# REV002.net
KiCad netlist of a schematic drawn in EAGLE
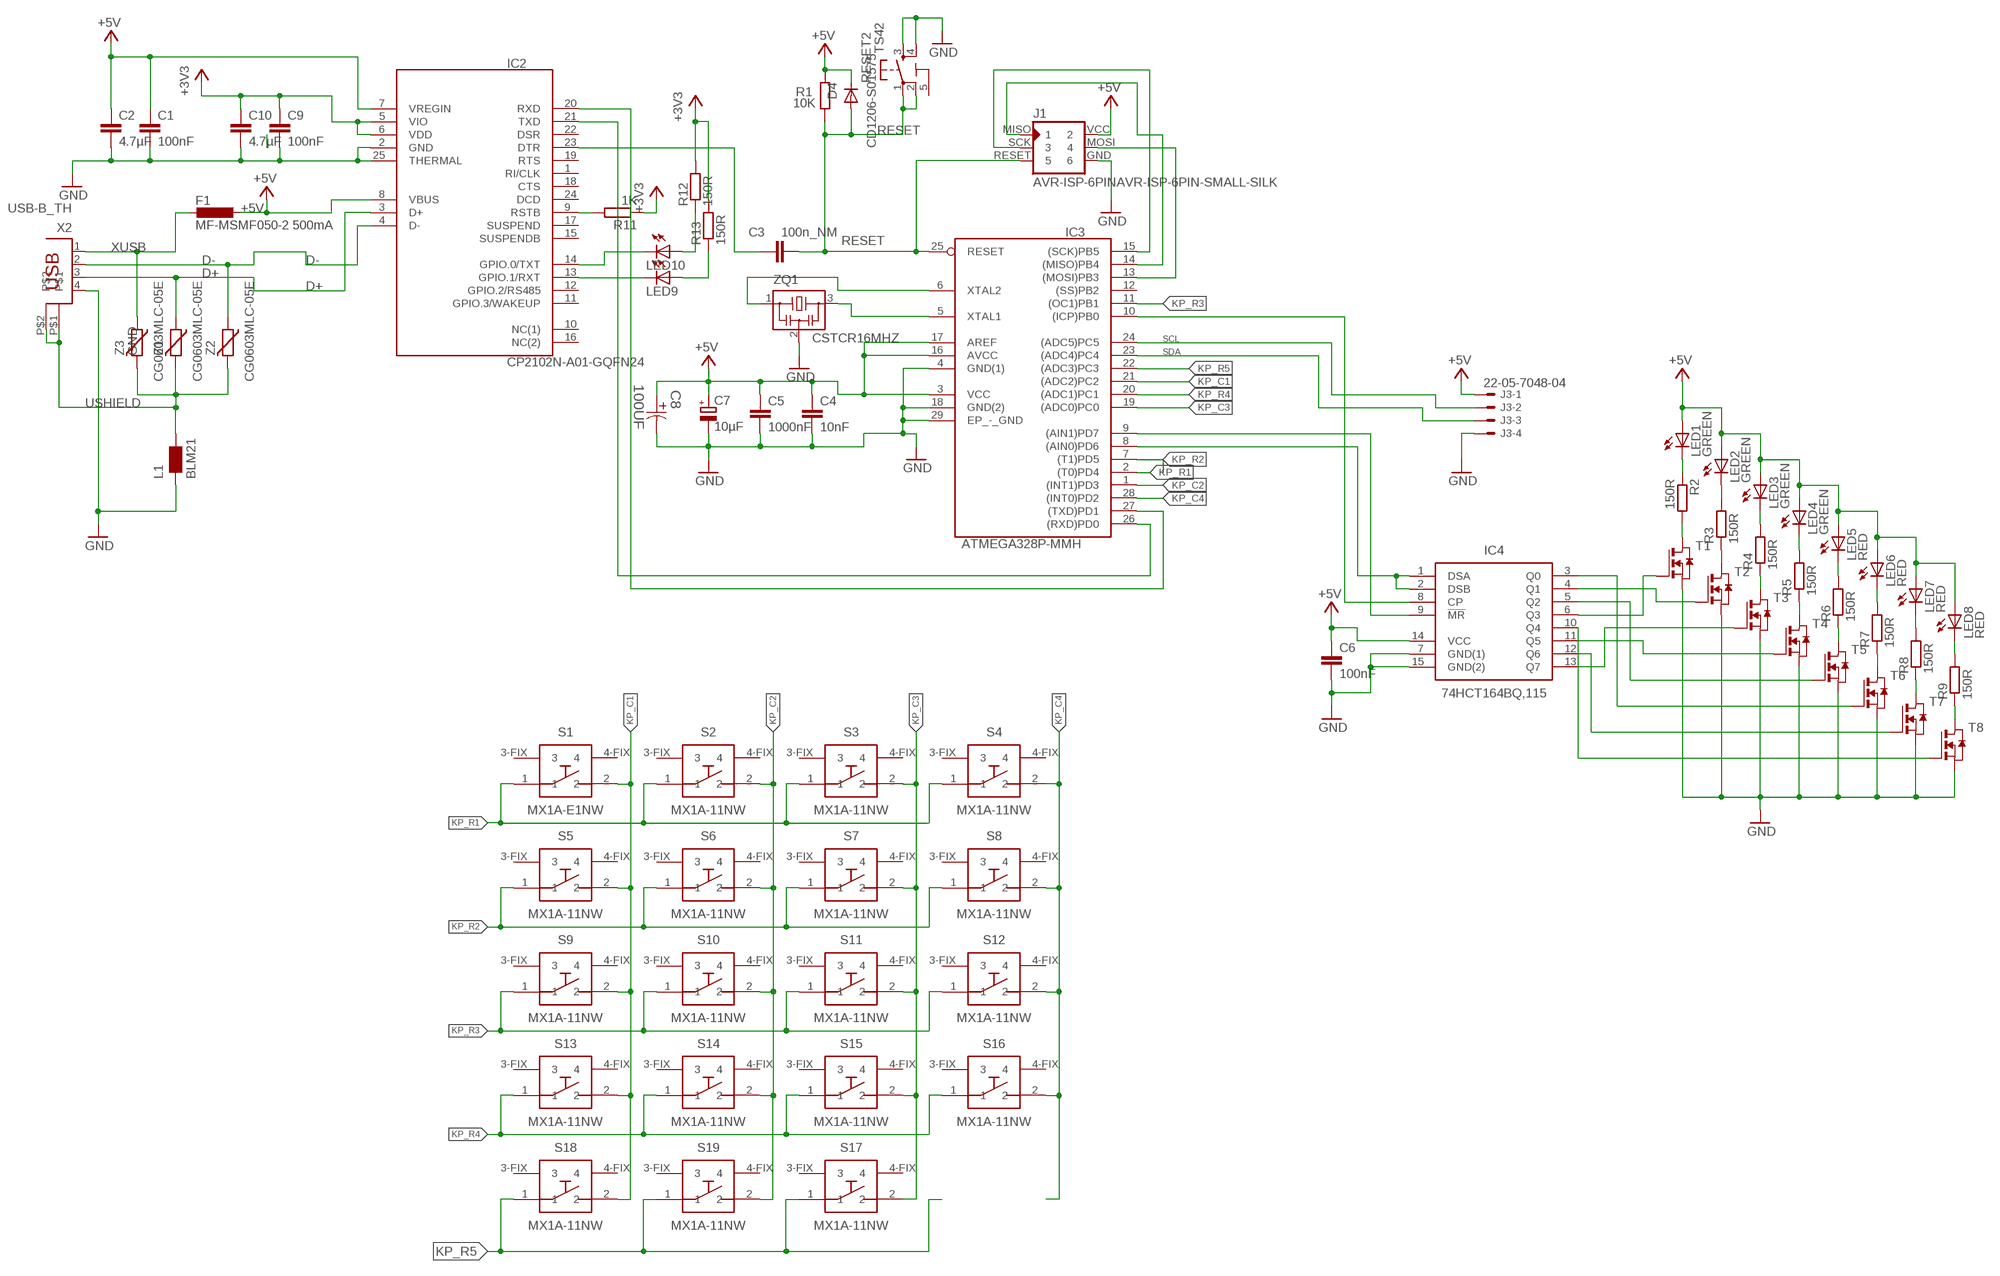
[diagram p0: schematic, sheet 1]

(export (version "E")
  (design (tool "Eeschema 10.0.6"))
  (components
    (comp (ref "C1")
      (value "100nF")
      (footprint "eagle-import:C0603K")
      (libsource (lib "eagle-import") (part "rcl_C-EUC0603K"))
    )
    (comp (ref "C2")
      (value "4.7µF")
      (footprint "eagle-import:C0603K")
      (libsource (lib "eagle-import") (part "rcl_C-EUC0603K"))
    )
    (comp (ref "C3")
      (value "100n_NM")
      (footprint "eagle-import:C0603K")
      (libsource (lib "eagle-import") (part "C-EUC0603K"))
    )
    (comp (ref "C4")
      (value "10nF")
      (footprint "eagle-import:C0603K")
      (libsource (lib "eagle-import") (part "rcl_C-EUC0603K"))
    )
    (comp (ref "C5")
      (value "1000nF")
      (footprint "eagle-import:C0603K")
      (libsource (lib "eagle-import") (part "rcl_C-EUC0603K"))
    )
    (comp (ref "C6")
      (value "100nF")
      (footprint "eagle-import:C0603K")
      (libsource (lib "eagle-import") (part "rcl_C-EUC0603K"))
    )
    (comp (ref "C7")
      (value "10µF")
      (footprint "eagle-import:SMC_B")
      (libsource (lib "eagle-import") (part "CPOL-EUSMCB"))
    )
    (comp (ref "C8")
      (value "100UF")
      (footprint "eagle-import:CAPAE430X610N")
      (fields (field (name "MPN") "EEE-FT0J101AR ") (field (name "TOLERANCE") "±20 %"))
      (libsource (lib "eagle-import") (part "EEE--CASE-BFT0J101AR"))
    )
    (comp (ref "C9")
      (value "100nF")
      (footprint "eagle-import:C0603K")
      (libsource (lib "eagle-import") (part "rcl_C-EUC0603K"))
    )
    (comp (ref "C10")
      (value "4.7µF")
      (footprint "eagle-import:C0603K")
      (libsource (lib "eagle-import") (part "rcl_C-EUC0603K"))
    )
    (comp (ref "D4")
      (value "CD1206-S01575")
      (footprint "eagle-import:MINIMELF")
      (libsource (lib "eagle-import") (part "DIODE-MINIMELF"))
    )
    (comp (ref "F1")
      (value "MF-MSMF050-2 500mA")
      (footprint "eagle-import:L1812")
      (libsource (lib "eagle-import") (part "L-EUL1812"))
    )
    (comp (ref "IC2")
      (value "CP2102N-A01-GQFN24")
      (footprint "eagle-import:QFN50P400X400X80-25N")
      (libsource (lib "eagle-import") (part "CP2102N-A01-GQFN24"))
    )
    (comp (ref "IC3")
      (value "ATMEGA328P-MMH")
      (footprint "eagle-import:QFN45P400X400X100-29N")
      (fields (field (name "RS_PART_NUMBER") "8149138P"))
      (libsource (lib "eagle-import") (part "ATMEGA328P-MMH"))
    )
    (comp (ref "IC4")
      (value "74HCT164BQ,115")
      (footprint "eagle-import:QFN50P300X250X100-15N")
      (libsource (lib "eagle-import") (part "74HCT164BQ,115"))
    )
    (comp (ref "J1")
      (value "AVR-ISP-6PINAVR-ISP-6PIN-SMALL-SILK")
      (footprint "eagle-import:AVR-ISP-6PIN-SMAILL-SILK")
      (libsource (lib "eagle-import") (part "AVR-ISP-6PINAVR-ISP-6PIN-SMALL-SILK"))
    )
    (comp (ref "J3")
      (value "22-05-7048-04")
      (footprint "eagle-import:7395-04")
      (libsource (lib "eagle-import") (part "22-?-0405-7048"))
    )
    (comp (ref "L1")
      (value "BLM21")
      (footprint "eagle-import:0805")
      (libsource (lib "eagle-import") (part "WE-CBF_0805"))
    )
    (comp (ref "LED1")
      (value "GREEN")
      (footprint "eagle-import:P-LCC-2")
      (libsource (lib "eagle-import") (part "LEDP-LCC-2"))
    )
    (comp (ref "LED2")
      (value "GREEN")
      (footprint "eagle-import:P-LCC-2")
      (libsource (lib "eagle-import") (part "LEDP-LCC-2"))
    )
    (comp (ref "LED3")
      (value "GREEN")
      (footprint "eagle-import:P-LCC-2")
      (libsource (lib "eagle-import") (part "LEDP-LCC-2"))
    )
    (comp (ref "LED4")
      (value "GREEN")
      (footprint "eagle-import:P-LCC-2")
      (libsource (lib "eagle-import") (part "LEDP-LCC-2"))
    )
    (comp (ref "LED5")
      (value "RED")
      (footprint "eagle-import:P-LCC-2")
      (libsource (lib "eagle-import") (part "LEDP-LCC-2"))
    )
    (comp (ref "LED6")
      (value "RED")
      (footprint "eagle-import:P-LCC-2")
      (libsource (lib "eagle-import") (part "LEDP-LCC-2"))
    )
    (comp (ref "LED7")
      (value "RED")
      (footprint "eagle-import:P-LCC-2")
      (libsource (lib "eagle-import") (part "LEDP-LCC-2"))
    )
    (comp (ref "LED8")
      (value "RED")
      (footprint "eagle-import:P-LCC-2")
      (libsource (lib "eagle-import") (part "LEDP-LCC-2"))
    )
    (comp (ref "LED9")
      (value "LEDCHIPLED_0603")
      (footprint "eagle-import:CHIPLED_0603")
      (libsource (lib "eagle-import") (part "led_LEDCHIPLED_0603"))
    )
    (comp (ref "LED10")
      (value "LEDCHIPLED_0603")
      (footprint "eagle-import:CHIPLED_0603")
      (libsource (lib "eagle-import") (part "led_LEDCHIPLED_0603"))
    )
    (comp (ref "R1")
      (value "10K")
      (footprint "eagle-import:R0603")
      (libsource (lib "eagle-import") (part "R-EU_R0603"))
    )
    (comp (ref "R2")
      (value "150R")
      (footprint "eagle-import:R0603")
      (libsource (lib "eagle-import") (part "R-EU_R0603"))
    )
    (comp (ref "R3")
      (value "150R")
      (footprint "eagle-import:R0603")
      (libsource (lib "eagle-import") (part "R-EU_R0603"))
    )
    (comp (ref "R4")
      (value "150R")
      (footprint "eagle-import:R0603")
      (libsource (lib "eagle-import") (part "R-EU_R0603"))
    )
    (comp (ref "R5")
      (value "150R")
      (footprint "eagle-import:R0603")
      (libsource (lib "eagle-import") (part "R-EU_R0603"))
    )
    (comp (ref "R6")
      (value "150R")
      (footprint "eagle-import:R0603")
      (libsource (lib "eagle-import") (part "R-EU_R0603"))
    )
    (comp (ref "R7")
      (value "150R")
      (footprint "eagle-import:R0603")
      (libsource (lib "eagle-import") (part "R-EU_R0603"))
    )
    (comp (ref "R8")
      (value "150R")
      (footprint "eagle-import:R0603")
      (libsource (lib "eagle-import") (part "R-EU_R0603"))
    )
    (comp (ref "R9")
      (value "150R")
      (footprint "eagle-import:R0603")
      (libsource (lib "eagle-import") (part "R-EU_R0603"))
    )
    (comp (ref "R11")
      (value "1K")
      (footprint "eagle-import:R0603")
      (libsource (lib "eagle-import") (part "R-EU_R0603"))
    )
    (comp (ref "R12")
      (value "150R")
      (footprint "eagle-import:R0603")
      (libsource (lib "eagle-import") (part "R-EU_R0603"))
    )
    (comp (ref "R13")
      (value "150R")
      (footprint "eagle-import:R0603")
      (libsource (lib "eagle-import") (part "R-EU_R0603"))
    )
    (comp (ref "RESET2")
      (value "TS42")
      (footprint "eagle-import:TS42")
      (libsource (lib "eagle-import") (part "TS42"))
    )
    (comp (ref "S1")
      (value "MX1A-E1NW")
      (footprint "eagle-import:MX1A-11NW_1")
      (fields (field (name "MANUFACTURER_PART_NUMBER") "MX1A-11NW"))
      (libsource (lib "eagle-import") (part "MX1A-11NW"))
    )
    (comp (ref "S2")
      (value "MX1A-11NW")
      (footprint "eagle-import:MX1A-11NW_1")
      (libsource (lib "eagle-import") (part "MX1A-11NW"))
    )
    (comp (ref "S3")
      (value "MX1A-11NW")
      (footprint "eagle-import:MX1A-11NW_1")
      (libsource (lib "eagle-import") (part "MX1A-11NW"))
    )
    (comp (ref "S4")
      (value "MX1A-11NW")
      (footprint "eagle-import:MX1A-11NW_1")
      (libsource (lib "eagle-import") (part "MX1A-11NW"))
    )
    (comp (ref "S5")
      (value "MX1A-11NW")
      (footprint "eagle-import:MX1A-11NW_1")
      (libsource (lib "eagle-import") (part "MX1A-11NW"))
    )
    (comp (ref "S6")
      (value "MX1A-11NW")
      (footprint "eagle-import:MX1A-11NW_1")
      (libsource (lib "eagle-import") (part "MX1A-11NW"))
    )
    (comp (ref "S7")
      (value "MX1A-11NW")
      (footprint "eagle-import:MX1A-11NW_1")
      (libsource (lib "eagle-import") (part "MX1A-11NW"))
    )
    (comp (ref "S8")
      (value "MX1A-11NW")
      (footprint "eagle-import:MX1A-11NW_1")
      (libsource (lib "eagle-import") (part "MX1A-11NW"))
    )
    (comp (ref "S9")
      (value "MX1A-11NW")
      (footprint "eagle-import:MX1A-11NW_1")
      (libsource (lib "eagle-import") (part "MX1A-11NW"))
    )
    (comp (ref "S10")
      (value "MX1A-11NW")
      (footprint "eagle-import:MX1A-11NW_1")
      (libsource (lib "eagle-import") (part "MX1A-11NW"))
    )
    (comp (ref "S11")
      (value "MX1A-11NW")
      (footprint "eagle-import:MX1A-11NW_1")
      (libsource (lib "eagle-import") (part "MX1A-11NW"))
    )
    (comp (ref "S12")
      (value "MX1A-11NW")
      (footprint "eagle-import:MX1A-11NW_1")
      (libsource (lib "eagle-import") (part "MX1A-11NW"))
    )
    (comp (ref "S13")
      (value "MX1A-11NW")
      (footprint "eagle-import:MX1A-11NW_1")
      (libsource (lib "eagle-import") (part "MX1A-11NW"))
    )
    (comp (ref "S14")
      (value "MX1A-11NW")
      (footprint "eagle-import:MX1A-11NW_1")
      (libsource (lib "eagle-import") (part "MX1A-11NW"))
    )
    (comp (ref "S15")
      (value "MX1A-11NW")
      (footprint "eagle-import:MX1A-11NW_1")
      (libsource (lib "eagle-import") (part "MX1A-11NW"))
    )
    (comp (ref "S16")
      (value "MX1A-11NW")
      (footprint "eagle-import:MX1A-11NW_1")
      (libsource (lib "eagle-import") (part "MX1A-11NW"))
    )
    (comp (ref "S17")
      (value "MX1A-11NW")
      (footprint "eagle-import:MX1A-11NW_1")
      (libsource (lib "eagle-import") (part "MX1A-11NW"))
    )
    (comp (ref "S18")
      (value "MX1A-11NW")
      (footprint "eagle-import:MX1A-11NW_1")
      (libsource (lib "eagle-import") (part "MX1A-11NW"))
    )
    (comp (ref "S19")
      (value "MX1A-11NW")
      (footprint "eagle-import:MX1A-11NW_1")
      (libsource (lib "eagle-import") (part "MX1A-11NW"))
    )
    (comp (ref "T1")
      (value "NMOSSOT23")
      (footprint "eagle-import:SOT-23")
      (libsource (lib "eagle-import") (part "NMOSSOT23"))
    )
    (comp (ref "T2")
      (value "NMOSSOT23")
      (footprint "eagle-import:SOT-23")
      (libsource (lib "eagle-import") (part "NMOSSOT23"))
    )
    (comp (ref "T3")
      (value "NMOSSOT23")
      (footprint "eagle-import:SOT-23")
      (libsource (lib "eagle-import") (part "NMOSSOT23"))
    )
    (comp (ref "T4")
      (value "NMOSSOT23")
      (footprint "eagle-import:SOT-23")
      (libsource (lib "eagle-import") (part "NMOSSOT23"))
    )
    (comp (ref "T5")
      (value "NMOSSOT23")
      (footprint "eagle-import:SOT-23")
      (libsource (lib "eagle-import") (part "NMOSSOT23"))
    )
    (comp (ref "T6")
      (value "NMOSSOT23")
      (footprint "eagle-import:SOT-23")
      (libsource (lib "eagle-import") (part "NMOSSOT23"))
    )
    (comp (ref "T7")
      (value "NMOSSOT23")
      (footprint "eagle-import:SOT-23")
      (libsource (lib "eagle-import") (part "NMOSSOT23"))
    )
    (comp (ref "T8")
      (value "NMOSSOT23")
      (footprint "eagle-import:SOT-23")
      (libsource (lib "eagle-import") (part "NMOSSOT23"))
    )
    (comp (ref "X2")
      (value "USB-B_TH")
      (footprint "eagle-import:PN61729")
      (libsource (lib "eagle-import") (part "PN61729"))
    )
    (comp (ref "Z1")
      (value "CG0603MLC-05E")
      (footprint "eagle-import:CT_CN0603")
      (libsource (lib "eagle-import") (part "VARISTORCN0603"))
    )
    (comp (ref "Z2")
      (value "CG0603MLC-05E")
      (footprint "eagle-import:CT_CN0603")
      (libsource (lib "eagle-import") (part "VARISTORCN0603"))
    )
    (comp (ref "Z3")
      (value "CG0603MLC-05E")
      (footprint "eagle-import:CT_CN0603")
      (libsource (lib "eagle-import") (part "VARISTORCN0603"))
    )
    (comp (ref "ZQ1")
      (value "CSTCR16MHZ")
      (footprint "eagle-import:CSTER12M")
      (libsource (lib "eagle-import") (part "CSTC?R"))
    )
  )
  (nets
    (net (code "1") (name "+3V3") (class "Default")
      (node (ref "C10") (pin "1") (pinfunction "1_1") (pintype "passive"))
      (node (ref "C9") (pin "1") (pinfunction "1_1") (pintype "passive"))
      (node (ref "IC2") (pin "5") (pinfunction "VIO_5") (pintype "input"))
      (node (ref "IC2") (pin "6") (pinfunction "VDD_6") (pintype "input"))
      (node (ref "R11") (pin "1") (pinfunction "1_1") (pintype "passive"))
      (node (ref "R12") (pin "2") (pinfunction "2_2") (pintype "passive"))
      (node (ref "R13") (pin "2") (pinfunction "2_2") (pintype "passive"))
    )
    (net (code "2") (name "+5V") (class "Default")
      (node (ref "C1") (pin "1") (pinfunction "1_1") (pintype "passive"))
      (node (ref "C2") (pin "1") (pinfunction "1_1") (pintype "passive"))
      (node (ref "C4") (pin "1") (pinfunction "1_1") (pintype "passive"))
      (node (ref "C5") (pin "1") (pinfunction "1_1") (pintype "passive"))
      (node (ref "C6") (pin "1") (pinfunction "1_1") (pintype "passive"))
      (node (ref "C7") (pin "+") (pinfunction "+_+") (pintype "passive"))
      (node (ref "C8") (pin "1") (pinfunction "1_1") (pintype "passive"))
      (node (ref "D4") (pin "C") (pinfunction "C_C") (pintype "passive"))
      (node (ref "F1") (pin "1") (pinfunction "1_1") (pintype "passive"))
      (node (ref "IC2") (pin "7") (pinfunction "VREGIN_7") (pintype "input"))
      (node (ref "IC2") (pin "8") (pinfunction "VBUS_8") (pintype "input"))
      (node (ref "IC3") (pin "16") (pinfunction "AVCC_16") (pintype "input"))
      (node (ref "IC3") (pin "17") (pinfunction "AREF_17") (pintype "input"))
      (node (ref "IC3") (pin "3") (pinfunction "VCC_3") (pintype "input"))
      (node (ref "IC4") (pin "14") (pinfunction "VCC_14") (pintype "input"))
      (node (ref "J1") (pin "VCC") (pinfunction "2_VCC") (pintype "passive"))
      (node (ref "J3") (pin "1") (pinfunction "S_1") (pintype "passive"))
      (node (ref "LED1") (pin "A") (pinfunction "A_A") (pintype "passive"))
      (node (ref "LED2") (pin "A") (pinfunction "A_A") (pintype "passive"))
      (node (ref "LED3") (pin "A") (pinfunction "A_A") (pintype "passive"))
      (node (ref "LED4") (pin "A") (pinfunction "A_A") (pintype "passive"))
      (node (ref "LED5") (pin "A") (pinfunction "A_A") (pintype "passive"))
      (node (ref "LED6") (pin "A") (pinfunction "A_A") (pintype "passive"))
      (node (ref "LED7") (pin "A") (pinfunction "A_A") (pintype "passive"))
      (node (ref "LED8") (pin "A") (pinfunction "A_A") (pintype "passive"))
      (node (ref "R1") (pin "2") (pinfunction "2_2") (pintype "passive"))
    )
    (net (code "3") (name "/5-GND") (class "Default")
      (node (ref "RESET2") (pin "5") (pinfunction "5-GND_5") (pintype "power_in"))
    )
    (net (code "4") (name "/D+") (class "Default")
      (node (ref "IC2") (pin "3") (pinfunction "D+_3") (pintype "input"))
      (node (ref "X2") (pin "3") (pinfunction "3_3") (pintype "bidirectional"))
      (node (ref "Z1") (pin "1") (pinfunction "1_1") (pintype "passive"))
    )
    (net (code "5") (name "/D-") (class "Default")
      (node (ref "IC2") (pin "4") (pinfunction "D-_4") (pintype "input"))
      (node (ref "X2") (pin "2") (pinfunction "2_2") (pintype "bidirectional"))
      (node (ref "Z2") (pin "1") (pinfunction "1_1") (pintype "passive"))
    )
    (net (code "6") (name "/RESET") (class "Default")
      (node (ref "C3") (pin "1") (pinfunction "1_1") (pintype "passive"))
      (node (ref "D4") (pin "A") (pinfunction "A_A") (pintype "passive"))
      (node (ref "IC3") (pin "25") (pinfunction "RESET_25") (pintype "input"))
      (node (ref "J1") (pin "RESET") (pinfunction "5_RESET") (pintype "passive"))
      (node (ref "R1") (pin "1") (pinfunction "1_1") (pintype "passive"))
      (node (ref "RESET2") (pin "1") (pinfunction "1_1") (pintype "passive"))
      (node (ref "RESET2") (pin "2") (pinfunction "2_2") (pintype "passive"))
    )
    (net (code "7") (name "/SCL") (class "Default")
      (node (ref "IC3") (pin "24") (pinfunction "(ADC5)PC5_24") (pintype "input"))
      (node (ref "J3") (pin "2") (pinfunction "S_2") (pintype "passive"))
    )
    (net (code "8") (name "/SDA") (class "Default")
      (node (ref "IC3") (pin "23") (pinfunction "(ADC4)PC4_23") (pintype "input"))
      (node (ref "J3") (pin "3") (pinfunction "S_3") (pintype "passive"))
    )
    (net (code "9") (name "/USHIELD") (class "Default")
      (node (ref "L1") (pin "2") (pinfunction "2_2") (pintype "passive"))
      (node (ref "X2") (pin "P$1") (pinfunction "P$1_P$1") (pintype "bidirectional"))
      (node (ref "X2") (pin "P$2") (pinfunction "P$2_P$2") (pintype "bidirectional"))
      (node (ref "Z1") (pin "2") (pinfunction "2_2") (pintype "passive"))
      (node (ref "Z2") (pin "2") (pinfunction "2_2") (pintype "passive"))
      (node (ref "Z3") (pin "2") (pinfunction "2_2") (pintype "passive"))
    )
    (net (code "10") (name "/XUSB") (class "Default")
      (node (ref "F1") (pin "2") (pinfunction "2_2") (pintype "passive"))
      (node (ref "X2") (pin "1") (pinfunction "1_1") (pintype "bidirectional"))
      (node (ref "Z3") (pin "1") (pinfunction "1_1") (pintype "passive"))
    )
    (net (code "11") (name "GND") (class "Default")
      (node (ref "C1") (pin "2") (pinfunction "2_2") (pintype "passive"))
      (node (ref "C10") (pin "2") (pinfunction "2_2") (pintype "passive"))
      (node (ref "C2") (pin "2") (pinfunction "2_2") (pintype "passive"))
      (node (ref "C4") (pin "2") (pinfunction "2_2") (pintype "passive"))
      (node (ref "C5") (pin "2") (pinfunction "2_2") (pintype "passive"))
      (node (ref "C6") (pin "2") (pinfunction "2_2") (pintype "passive"))
      (node (ref "C7") (pin "-") (pinfunction "-_-") (pintype "passive"))
      (node (ref "C8") (pin "2") (pinfunction "2_2") (pintype "passive"))
      (node (ref "C9") (pin "2") (pinfunction "2_2") (pintype "passive"))
      (node (ref "IC2") (pin "2") (pinfunction "GND_2") (pintype "input"))
      (node (ref "IC2") (pin "25") (pinfunction "THERMAL_25") (pintype "input"))
      (node (ref "IC3") (pin "18") (pinfunction "GND(2)_18") (pintype "input"))
      (node (ref "IC3") (pin "29") (pinfunction "EP_-_GND_29") (pintype "input"))
      (node (ref "IC3") (pin "4") (pinfunction "GND(1)_4") (pintype "input"))
      (node (ref "IC4") (pin "15") (pinfunction "GND(2)_15") (pintype "input"))
      (node (ref "IC4") (pin "7") (pinfunction "GND(1)_7") (pintype "input"))
      (node (ref "J1") (pin "GND") (pinfunction "6_GND") (pintype "passive"))
      (node (ref "J3") (pin "4") (pinfunction "S_4") (pintype "passive"))
      (node (ref "L1") (pin "1") (pinfunction "1_1") (pintype "passive"))
      (node (ref "RESET2") (pin "3") (pinfunction "3_3") (pintype "passive"))
      (node (ref "RESET2") (pin "4") (pinfunction "4_4") (pintype "passive"))
      (node (ref "T1") (pin "2") (pinfunction "S_2") (pintype "passive"))
      (node (ref "T2") (pin "2") (pinfunction "S_2") (pintype "passive"))
      (node (ref "T3") (pin "2") (pinfunction "S_2") (pintype "passive"))
      (node (ref "T4") (pin "2") (pinfunction "S_2") (pintype "passive"))
      (node (ref "T5") (pin "2") (pinfunction "S_2") (pintype "passive"))
      (node (ref "T6") (pin "2") (pinfunction "S_2") (pintype "passive"))
      (node (ref "T7") (pin "2") (pinfunction "S_2") (pintype "passive"))
      (node (ref "T8") (pin "2") (pinfunction "S_2") (pintype "passive"))
      (node (ref "X2") (pin "4") (pinfunction "4_4") (pintype "bidirectional"))
      (node (ref "ZQ1") (pin "2") (pinfunction "2_2") (pintype "passive"))
    )
    (net (code "12") (name "KP_C1") (class "Default")
      (node (ref "IC3") (pin "21") (pinfunction "(ADC2)PC2_21") (pintype "input"))
      (node (ref "S1") (pin "2") (pinfunction "2_2") (pintype "input"))
      (node (ref "S13") (pin "2") (pinfunction "2_2") (pintype "input"))
      (node (ref "S18") (pin "2") (pinfunction "2_2") (pintype "input"))
      (node (ref "S5") (pin "2") (pinfunction "2_2") (pintype "input"))
      (node (ref "S9") (pin "2") (pinfunction "2_2") (pintype "input"))
    )
    (net (code "13") (name "KP_C2") (class "Default")
      (node (ref "IC3") (pin "1") (pinfunction "(INT1)PD3_1") (pintype "input"))
      (node (ref "S10") (pin "2") (pinfunction "2_2") (pintype "input"))
      (node (ref "S14") (pin "2") (pinfunction "2_2") (pintype "input"))
      (node (ref "S19") (pin "2") (pinfunction "2_2") (pintype "input"))
      (node (ref "S2") (pin "2") (pinfunction "2_2") (pintype "input"))
      (node (ref "S6") (pin "2") (pinfunction "2_2") (pintype "input"))
    )
    (net (code "14") (name "KP_C3") (class "Default")
      (node (ref "IC3") (pin "19") (pinfunction "(ADC0)PC0_19") (pintype "input"))
      (node (ref "S11") (pin "2") (pinfunction "2_2") (pintype "input"))
      (node (ref "S15") (pin "2") (pinfunction "2_2") (pintype "input"))
      (node (ref "S17") (pin "2") (pinfunction "2_2") (pintype "input"))
      (node (ref "S3") (pin "2") (pinfunction "2_2") (pintype "input"))
      (node (ref "S7") (pin "2") (pinfunction "2_2") (pintype "input"))
    )
    (net (code "15") (name "KP_C4") (class "Default")
      (node (ref "IC3") (pin "28") (pinfunction "(INT0)PD2_28") (pintype "input"))
      (node (ref "S12") (pin "2") (pinfunction "2_2") (pintype "input"))
      (node (ref "S16") (pin "2") (pinfunction "2_2") (pintype "input"))
      (node (ref "S4") (pin "2") (pinfunction "2_2") (pintype "input"))
      (node (ref "S8") (pin "2") (pinfunction "2_2") (pintype "input"))
    )
    (net (code "16") (name "KP_R1") (class "Default")
      (node (ref "IC3") (pin "2") (pinfunction "(T0)PD4_2") (pintype "input"))
      (node (ref "S1") (pin "1") (pinfunction "1_1") (pintype "input"))
      (node (ref "S2") (pin "1") (pinfunction "1_1") (pintype "input"))
      (node (ref "S3") (pin "1") (pinfunction "1_1") (pintype "input"))
      (node (ref "S4") (pin "1") (pinfunction "1_1") (pintype "input"))
    )
    (net (code "17") (name "KP_R2") (class "Default")
      (node (ref "IC3") (pin "7") (pinfunction "(T1)PD5_7") (pintype "input"))
      (node (ref "S5") (pin "1") (pinfunction "1_1") (pintype "input"))
      (node (ref "S6") (pin "1") (pinfunction "1_1") (pintype "input"))
      (node (ref "S7") (pin "1") (pinfunction "1_1") (pintype "input"))
      (node (ref "S8") (pin "1") (pinfunction "1_1") (pintype "input"))
    )
    (net (code "18") (name "KP_R3") (class "Default")
      (node (ref "IC3") (pin "11") (pinfunction "(OC1)PB1_11") (pintype "input"))
      (node (ref "S10") (pin "1") (pinfunction "1_1") (pintype "input"))
      (node (ref "S11") (pin "1") (pinfunction "1_1") (pintype "input"))
      (node (ref "S12") (pin "1") (pinfunction "1_1") (pintype "input"))
      (node (ref "S9") (pin "1") (pinfunction "1_1") (pintype "input"))
    )
    (net (code "19") (name "KP_R4") (class "Default")
      (node (ref "IC3") (pin "20") (pinfunction "(ADC1)PC1_20") (pintype "input"))
      (node (ref "S13") (pin "1") (pinfunction "1_1") (pintype "input"))
      (node (ref "S14") (pin "1") (pinfunction "1_1") (pintype "input"))
      (node (ref "S15") (pin "1") (pinfunction "1_1") (pintype "input"))
      (node (ref "S16") (pin "1") (pinfunction "1_1") (pintype "input"))
    )
    (net (code "20") (name "KP_R5") (class "Default")
      (node (ref "IC3") (pin "22") (pinfunction "(ADC3)PC3_22") (pintype "input"))
      (node (ref "S17") (pin "1") (pinfunction "1_1") (pintype "input"))
      (node (ref "S18") (pin "1") (pinfunction "1_1") (pintype "input"))
      (node (ref "S19") (pin "1") (pinfunction "1_1") (pintype "input"))
    )
    (net (code "21") (name "Net-(IC2-DTR)") (class "Default")
      (node (ref "C3") (pin "2") (pinfunction "2_2") (pintype "passive"))
      (node (ref "IC2") (pin "23") (pinfunction "DTR_23") (pintype "input"))
    )
    (net (code "22") (name "Net-(IC2-GPIO.0{slash}TXT)") (class "Default")
      (node (ref "IC2") (pin "14") (pinfunction "GPIO.0/TXT_14") (pintype "input"))
      (node (ref "LED10") (pin "C") (pinfunction "C_C") (pintype "passive"))
    )
    (net (code "23") (name "Net-(IC2-GPIO.1{slash}RXT)") (class "Default")
      (node (ref "IC2") (pin "13") (pinfunction "GPIO.1/RXT_13") (pintype "input"))
      (node (ref "LED9") (pin "C") (pinfunction "C_C") (pintype "passive"))
    )
    (net (code "24") (name "Net-(IC2-RSTB)") (class "Default")
      (node (ref "IC2") (pin "9") (pinfunction "RSTB_9") (pintype "input"))
      (node (ref "R11") (pin "2") (pinfunction "2_2") (pintype "passive"))
    )
    (net (code "25") (name "Net-(IC2-RXD)") (class "Default")
      (node (ref "IC2") (pin "20") (pinfunction "RXD_20") (pintype "input"))
      (node (ref "IC3") (pin "27") (pinfunction "(TXD)PD1_27") (pintype "input"))
    )
    (net (code "26") (name "Net-(IC2-TXD)") (class "Default")
      (node (ref "IC2") (pin "21") (pinfunction "TXD_21") (pintype "input"))
      (node (ref "IC3") (pin "26") (pinfunction "(RXD)PD0_26") (pintype "input"))
    )
    (net (code "27") (name "Net-(IC3-(AIN0)PD6)") (class "Default")
      (node (ref "IC3") (pin "8") (pinfunction "(AIN0)PD6_8") (pintype "input"))
      (node (ref "IC4") (pin "1") (pinfunction "DSA_1") (pintype "input"))
      (node (ref "IC4") (pin "2") (pinfunction "DSB_2") (pintype "input"))
    )
    (net (code "28") (name "Net-(IC3-(AIN1)PD7)") (class "Default")
      (node (ref "IC3") (pin "9") (pinfunction "(AIN1)PD7_9") (pintype "input"))
      (node (ref "IC4") (pin "9") (pinfunction "~{MR}_9") (pintype "input"))
    )
    (net (code "29") (name "Net-(IC3-(ICP)PB0)") (class "Default")
      (node (ref "IC3") (pin "10") (pinfunction "(ICP)PB0_10") (pintype "input"))
      (node (ref "IC4") (pin "8") (pinfunction "CP_8") (pintype "input"))
    )
    (net (code "30") (name "Net-(IC3-(MISO)PB4)") (class "Default")
      (node (ref "IC3") (pin "14") (pinfunction "(MISO)PB4_14") (pintype "input"))
      (node (ref "J1") (pin "MISO") (pinfunction "1_MISO") (pintype "passive"))
    )
    (net (code "31") (name "Net-(IC3-(MOSI)PB3)") (class "Default")
      (node (ref "IC3") (pin "13") (pinfunction "(MOSI)PB3_13") (pintype "input"))
      (node (ref "J1") (pin "MOSI") (pinfunction "4_MOSI") (pintype "passive"))
    )
    (net (code "32") (name "Net-(IC3-(SCK)PB5)") (class "Default")
      (node (ref "IC3") (pin "15") (pinfunction "(SCK)PB5_15") (pintype "input"))
      (node (ref "J1") (pin "SCK") (pinfunction "3_SCK") (pintype "passive"))
    )
    (net (code "33") (name "Net-(IC3-XTAL1)") (class "Default")
      (node (ref "IC3") (pin "5") (pinfunction "XTAL1_5") (pintype "input"))
      (node (ref "ZQ1") (pin "3") (pinfunction "3_3") (pintype "passive"))
    )
    (net (code "34") (name "Net-(IC3-XTAL2)") (class "Default")
      (node (ref "IC3") (pin "6") (pinfunction "XTAL2_6") (pintype "input"))
      (node (ref "ZQ1") (pin "1") (pinfunction "1_1") (pintype "passive"))
    )
    (net (code "35") (name "Net-(IC4-Q0)") (class "Default")
      (node (ref "IC4") (pin "3") (pinfunction "Q0_3") (pintype "input"))
      (node (ref "T6") (pin "3") (pinfunction "G_3") (pintype "passive"))
    )
    (net (code "36") (name "Net-(IC4-Q1)") (class "Default")
      (node (ref "IC4") (pin "4") (pinfunction "Q1_4") (pintype "input"))
      (node (ref "T2") (pin "3") (pinfunction "G_3") (pintype "passive"))
    )
    (net (code "37") (name "Net-(IC4-Q2)") (class "Default")
      (node (ref "IC4") (pin "5") (pinfunction "Q2_5") (pintype "input"))
      (node (ref "T5") (pin "3") (pinfunction "G_3") (pintype "passive"))
    )
    (net (code "38") (name "Net-(IC4-Q3)") (class "Default")
      (node (ref "IC4") (pin "6") (pinfunction "Q3_6") (pintype "input"))
      (node (ref "T1") (pin "3") (pinfunction "G_3") (pintype "passive"))
    )
    (net (code "39") (name "Net-(IC4-Q4)") (class "Default")
      (node (ref "IC4") (pin "10") (pinfunction "Q4_10") (pintype "input"))
      (node (ref "T8") (pin "3") (pinfunction "G_3") (pintype "passive"))
    )
    (net (code "40") (name "Net-(IC4-Q5)") (class "Default")
      (node (ref "IC4") (pin "11") (pinfunction "Q5_11") (pintype "input"))
      (node (ref "T4") (pin "3") (pinfunction "G_3") (pintype "passive"))
    )
    (net (code "41") (name "Net-(IC4-Q6)") (class "Default")
      (node (ref "IC4") (pin "12") (pinfunction "Q6_12") (pintype "input"))
      (node (ref "T7") (pin "3") (pinfunction "G_3") (pintype "passive"))
    )
    (net (code "42") (name "Net-(IC4-Q7)") (class "Default")
      (node (ref "IC4") (pin "13") (pinfunction "Q7_13") (pintype "input"))
      (node (ref "T3") (pin "3") (pinfunction "G_3") (pintype "passive"))
    )
    (net (code "43") (name "Net-(LED1-PadC)") (class "Default")
      (node (ref "LED1") (pin "C") (pinfunction "C_C") (pintype "passive"))
      (node (ref "R2") (pin "1") (pinfunction "1_1") (pintype "passive"))
    )
    (net (code "44") (name "Net-(LED2-PadC)") (class "Default")
      (node (ref "LED2") (pin "C") (pinfunction "C_C") (pintype "passive"))
      (node (ref "R3") (pin "2") (pinfunction "2_2") (pintype "passive"))
    )
    (net (code "45") (name "Net-(LED3-PadC)") (class "Default")
      (node (ref "LED3") (pin "C") (pinfunction "C_C") (pintype "passive"))
      (node (ref "R4") (pin "2") (pinfunction "2_2") (pintype "passive"))
    )
    (net (code "46") (name "Net-(LED4-PadC)") (class "Default")
      (node (ref "LED4") (pin "C") (pinfunction "C_C") (pintype "passive"))
      (node (ref "R5") (pin "2") (pinfunction "2_2") (pintype "passive"))
    )
    (net (code "47") (name "Net-(LED5-PadC)") (class "Default")
      (node (ref "LED5") (pin "C") (pinfunction "C_C") (pintype "passive"))
      (node (ref "R6") (pin "2") (pinfunction "2_2") (pintype "passive"))
    )
    (net (code "48") (name "Net-(LED6-PadC)") (class "Default")
      (node (ref "LED6") (pin "C") (pinfunction "C_C") (pintype "passive"))
      (node (ref "R7") (pin "2") (pinfunction "2_2") (pintype "passive"))
    )
    (net (code "49") (name "Net-(LED7-PadC)") (class "Default")
      (node (ref "LED7") (pin "C") (pinfunction "C_C") (pintype "passive"))
      (node (ref "R8") (pin "2") (pinfunction "2_2") (pintype "passive"))
    )
    (net (code "50") (name "Net-(LED8-PadC)") (class "Default")
      (node (ref "LED8") (pin "C") (pinfunction "C_C") (pintype "passive"))
      (node (ref "R9") (pin "2") (pinfunction "2_2") (pintype "passive"))
    )
    (net (code "51") (name "Net-(LED9-PadA)") (class "Default")
      (node (ref "LED9") (pin "A") (pinfunction "A_A") (pintype "passive"))
      (node (ref "R13") (pin "1") (pinfunction "1_1") (pintype "passive"))
    )
    (net (code "52") (name "Net-(LED10-PadA)") (class "Default")
      (node (ref "LED10") (pin "A") (pinfunction "A_A") (pintype "passive"))
      (node (ref "R12") (pin "1") (pinfunction "1_1") (pintype "passive"))
    )
    (net (code "53") (name "Net-(T1-D)") (class "Default")
      (node (ref "R2") (pin "2") (pinfunction "2_2") (pintype "passive"))
      (node (ref "T1") (pin "1") (pinfunction "D_1") (pintype "passive"))
    )
    (net (code "54") (name "Net-(T2-D)") (class "Default")
      (node (ref "R3") (pin "1") (pinfunction "1_1") (pintype "passive"))
      (node (ref "T2") (pin "1") (pinfunction "D_1") (pintype "passive"))
    )
    (net (code "55") (name "Net-(T3-D)") (class "Default")
      (node (ref "R4") (pin "1") (pinfunction "1_1") (pintype "passive"))
      (node (ref "T3") (pin "1") (pinfunction "D_1") (pintype "passive"))
    )
    (net (code "56") (name "Net-(T4-D)") (class "Default")
      (node (ref "R5") (pin "1") (pinfunction "1_1") (pintype "passive"))
      (node (ref "T4") (pin "1") (pinfunction "D_1") (pintype "passive"))
    )
    (net (code "57") (name "Net-(T5-D)") (class "Default")
      (node (ref "R6") (pin "1") (pinfunction "1_1") (pintype "passive"))
      (node (ref "T5") (pin "1") (pinfunction "D_1") (pintype "passive"))
    )
    (net (code "58") (name "Net-(T6-D)") (class "Default")
      (node (ref "R7") (pin "1") (pinfunction "1_1") (pintype "passive"))
      (node (ref "T6") (pin "1") (pinfunction "D_1") (pintype "passive"))
    )
    (net (code "59") (name "Net-(T7-D)") (class "Default")
      (node (ref "R8") (pin "1") (pinfunction "1_1") (pintype "passive"))
      (node (ref "T7") (pin "1") (pinfunction "D_1") (pintype "passive"))
    )
    (net (code "60") (name "Net-(T8-D)") (class "Default")
      (node (ref "R9") (pin "1") (pinfunction "1_1") (pintype "passive"))
      (node (ref "T8") (pin "1") (pinfunction "D_1") (pintype "passive"))
    )
    (net (code "61") (name "unconnected-(IC2-CTS-Pad18)") (class "Default")
      (node (ref "IC2") (pin "18") (pinfunction "CTS_18") (pintype "input"))
    )
    (net (code "62") (name "unconnected-(IC2-DCD-Pad24)") (class "Default")
      (node (ref "IC2") (pin "24") (pinfunction "DCD_24") (pintype "input"))
    )
    (net (code "63") (name "unconnected-(IC2-DSR-Pad22)") (class "Default")
      (node (ref "IC2") (pin "22") (pinfunction "DSR_22") (pintype "input"))
    )
    (net (code "64") (name "unconnected-(IC2-GPIO.2{slash}RS485-Pad12)") (class "Default")
      (node (ref "IC2") (pin "12") (pinfunction "GPIO.2/RS485_12") (pintype "input"))
    )
    (net (code "65") (name "unconnected-(IC2-GPIO.3{slash}WAKEUP-Pad11)") (class "Default")
      (node (ref "IC2") (pin "11") (pinfunction "GPIO.3/WAKEUP_11") (pintype "input"))
    )
    (net (code "66") (name "unconnected-(IC2-NC(1)-Pad10)") (class "Default")
      (node (ref "IC2") (pin "10") (pinfunction "NC(1)_10") (pintype "input"))
    )
    (net (code "67") (name "unconnected-(IC2-NC(2)-Pad16)") (class "Default")
      (node (ref "IC2") (pin "16") (pinfunction "NC(2)_16") (pintype "input"))
    )
    (net (code "68") (name "unconnected-(IC2-RI{slash}CLK-Pad1)") (class "Default")
      (node (ref "IC2") (pin "1") (pinfunction "RI/CLK_1") (pintype "input"))
    )
    (net (code "69") (name "unconnected-(IC2-RTS-Pad19)") (class "Default")
      (node (ref "IC2") (pin "19") (pinfunction "RTS_19") (pintype "input"))
    )
    (net (code "70") (name "unconnected-(IC2-SUSPEND-Pad17)") (class "Default")
      (node (ref "IC2") (pin "17") (pinfunction "SUSPEND_17") (pintype "input"))
    )
    (net (code "71") (name "unconnected-(IC2-SUSPENDB-Pad15)") (class "Default")
      (node (ref "IC2") (pin "15") (pinfunction "SUSPENDB_15") (pintype "input"))
    )
    (net (code "72") (name "unconnected-(IC3-(SS)PB2-Pad12)") (class "Default")
      (node (ref "IC3") (pin "12") (pinfunction "(SS)PB2_12") (pintype "input"))
    )
    (net (code "73") (name "unconnected-(S1-3-Pad3-FIX)") (class "Default")
      (node (ref "S1") (pin "3-FIX") (pinfunction "3_3-FIX") (pintype "input"))
    )
    (net (code "74") (name "unconnected-(S1-4-Pad4-FIX)") (class "Default")
      (node (ref "S1") (pin "4-FIX") (pinfunction "4_4-FIX") (pintype "input"))
    )
    (net (code "75") (name "unconnected-(S2-3-Pad3-FIX)") (class "Default")
      (node (ref "S2") (pin "3-FIX") (pinfunction "3_3-FIX") (pintype "input"))
    )
    (net (code "76") (name "unconnected-(S2-4-Pad4-FIX)") (class "Default")
      (node (ref "S2") (pin "4-FIX") (pinfunction "4_4-FIX") (pintype "input"))
    )
    (net (code "77") (name "unconnected-(S3-3-Pad3-FIX)") (class "Default")
      (node (ref "S3") (pin "3-FIX") (pinfunction "3_3-FIX") (pintype "input"))
    )
    (net (code "78") (name "unconnected-(S3-4-Pad4-FIX)") (class "Default")
      (node (ref "S3") (pin "4-FIX") (pinfunction "4_4-FIX") (pintype "input"))
    )
    (net (code "79") (name "unconnected-(S4-3-Pad3-FIX)") (class "Default")
      (node (ref "S4") (pin "3-FIX") (pinfunction "3_3-FIX") (pintype "input"))
    )
    (net (code "80") (name "unconnected-(S4-4-Pad4-FIX)") (class "Default")
      (node (ref "S4") (pin "4-FIX") (pinfunction "4_4-FIX") (pintype "input"))
    )
    (net (code "81") (name "unconnected-(S5-3-Pad3-FIX)") (class "Default")
      (node (ref "S5") (pin "3-FIX") (pinfunction "3_3-FIX") (pintype "input"))
    )
    (net (code "82") (name "unconnected-(S5-4-Pad4-FIX)") (class "Default")
      (node (ref "S5") (pin "4-FIX") (pinfunction "4_4-FIX") (pintype "input"))
    )
    (net (code "83") (name "unconnected-(S6-3-Pad3-FIX)") (class "Default")
      (node (ref "S6") (pin "3-FIX") (pinfunction "3_3-FIX") (pintype "input"))
    )
    (net (code "84") (name "unconnected-(S6-4-Pad4-FIX)") (class "Default")
      (node (ref "S6") (pin "4-FIX") (pinfunction "4_4-FIX") (pintype "input"))
    )
    (net (code "85") (name "unconnected-(S7-3-Pad3-FIX)") (class "Default")
      (node (ref "S7") (pin "3-FIX") (pinfunction "3_3-FIX") (pintype "input"))
    )
    (net (code "86") (name "unconnected-(S7-4-Pad4-FIX)") (class "Default")
      (node (ref "S7") (pin "4-FIX") (pinfunction "4_4-FIX") (pintype "input"))
    )
    (net (code "87") (name "unconnected-(S8-3-Pad3-FIX)") (class "Default")
      (node (ref "S8") (pin "3-FIX") (pinfunction "3_3-FIX") (pintype "input"))
    )
    (net (code "88") (name "unconnected-(S8-4-Pad4-FIX)") (class "Default")
      (node (ref "S8") (pin "4-FIX") (pinfunction "4_4-FIX") (pintype "input"))
    )
    (net (code "89") (name "unconnected-(S9-3-Pad3-FIX)") (class "Default")
      (node (ref "S9") (pin "3-FIX") (pinfunction "3_3-FIX") (pintype "input"))
    )
    (net (code "90") (name "unconnected-(S9-4-Pad4-FIX)") (class "Default")
      (node (ref "S9") (pin "4-FIX") (pinfunction "4_4-FIX") (pintype "input"))
    )
    (net (code "91") (name "unconnected-(S10-3-Pad3-FIX)") (class "Default")
      (node (ref "S10") (pin "3-FIX") (pinfunction "3_3-FIX") (pintype "input"))
    )
    (net (code "92") (name "unconnected-(S10-4-Pad4-FIX)") (class "Default")
      (node (ref "S10") (pin "4-FIX") (pinfunction "4_4-FIX") (pintype "input"))
    )
    (net (code "93") (name "unconnected-(S11-3-Pad3-FIX)") (class "Default")
      (node (ref "S11") (pin "3-FIX") (pinfunction "3_3-FIX") (pintype "input"))
    )
    (net (code "94") (name "unconnected-(S11-4-Pad4-FIX)") (class "Default")
      (node (ref "S11") (pin "4-FIX") (pinfunction "4_4-FIX") (pintype "input"))
    )
    (net (code "95") (name "unconnected-(S12-3-Pad3-FIX)") (class "Default")
      (node (ref "S12") (pin "3-FIX") (pinfunction "3_3-FIX") (pintype "input"))
    )
    (net (code "96") (name "unconnected-(S12-4-Pad4-FIX)") (class "Default")
      (node (ref "S12") (pin "4-FIX") (pinfunction "4_4-FIX") (pintype "input"))
    )
    (net (code "97") (name "unconnected-(S13-3-Pad3-FIX)") (class "Default")
      (node (ref "S13") (pin "3-FIX") (pinfunction "3_3-FIX") (pintype "input"))
    )
    (net (code "98") (name "unconnected-(S13-4-Pad4-FIX)") (class "Default")
      (node (ref "S13") (pin "4-FIX") (pinfunction "4_4-FIX") (pintype "input"))
    )
    (net (code "99") (name "unconnected-(S14-3-Pad3-FIX)") (class "Default")
      (node (ref "S14") (pin "3-FIX") (pinfunction "3_3-FIX") (pintype "input"))
    )
    (net (code "100") (name "unconnected-(S14-4-Pad4-FIX)") (class "Default")
      (node (ref "S14") (pin "4-FIX") (pinfunction "4_4-FIX") (pintype "input"))
    )
    (net (code "101") (name "unconnected-(S15-3-Pad3-FIX)") (class "Default")
      (node (ref "S15") (pin "3-FIX") (pinfunction "3_3-FIX") (pintype "input"))
    )
    (net (code "102") (name "unconnected-(S15-4-Pad4-FIX)") (class "Default")
      (node (ref "S15") (pin "4-FIX") (pinfunction "4_4-FIX") (pintype "input"))
    )
    (net (code "103") (name "unconnected-(S16-3-Pad3-FIX)") (class "Default")
      (node (ref "S16") (pin "3-FIX") (pinfunction "3_3-FIX") (pintype "input"))
    )
    (net (code "104") (name "unconnected-(S16-4-Pad4-FIX)") (class "Default")
      (node (ref "S16") (pin "4-FIX") (pinfunction "4_4-FIX") (pintype "input"))
    )
    (net (code "105") (name "unconnected-(S17-3-Pad3-FIX)") (class "Default")
      (node (ref "S17") (pin "3-FIX") (pinfunction "3_3-FIX") (pintype "input"))
    )
    (net (code "106") (name "unconnected-(S17-4-Pad4-FIX)") (class "Default")
      (node (ref "S17") (pin "4-FIX") (pinfunction "4_4-FIX") (pintype "input"))
    )
    (net (code "107") (name "unconnected-(S18-3-Pad3-FIX)") (class "Default")
      (node (ref "S18") (pin "3-FIX") (pinfunction "3_3-FIX") (pintype "input"))
    )
    (net (code "108") (name "unconnected-(S18-4-Pad4-FIX)") (class "Default")
      (node (ref "S18") (pin "4-FIX") (pinfunction "4_4-FIX") (pintype "input"))
    )
    (net (code "109") (name "unconnected-(S19-3-Pad3-FIX)") (class "Default")
      (node (ref "S19") (pin "3-FIX") (pinfunction "3_3-FIX") (pintype "input"))
    )
    (net (code "110") (name "unconnected-(S19-4-Pad4-FIX)") (class "Default")
      (node (ref "S19") (pin "4-FIX") (pinfunction "4_4-FIX") (pintype "input"))
    )
  )
)
